# circuit.net
KiCad netlist of a schematic drawn in EAGLE
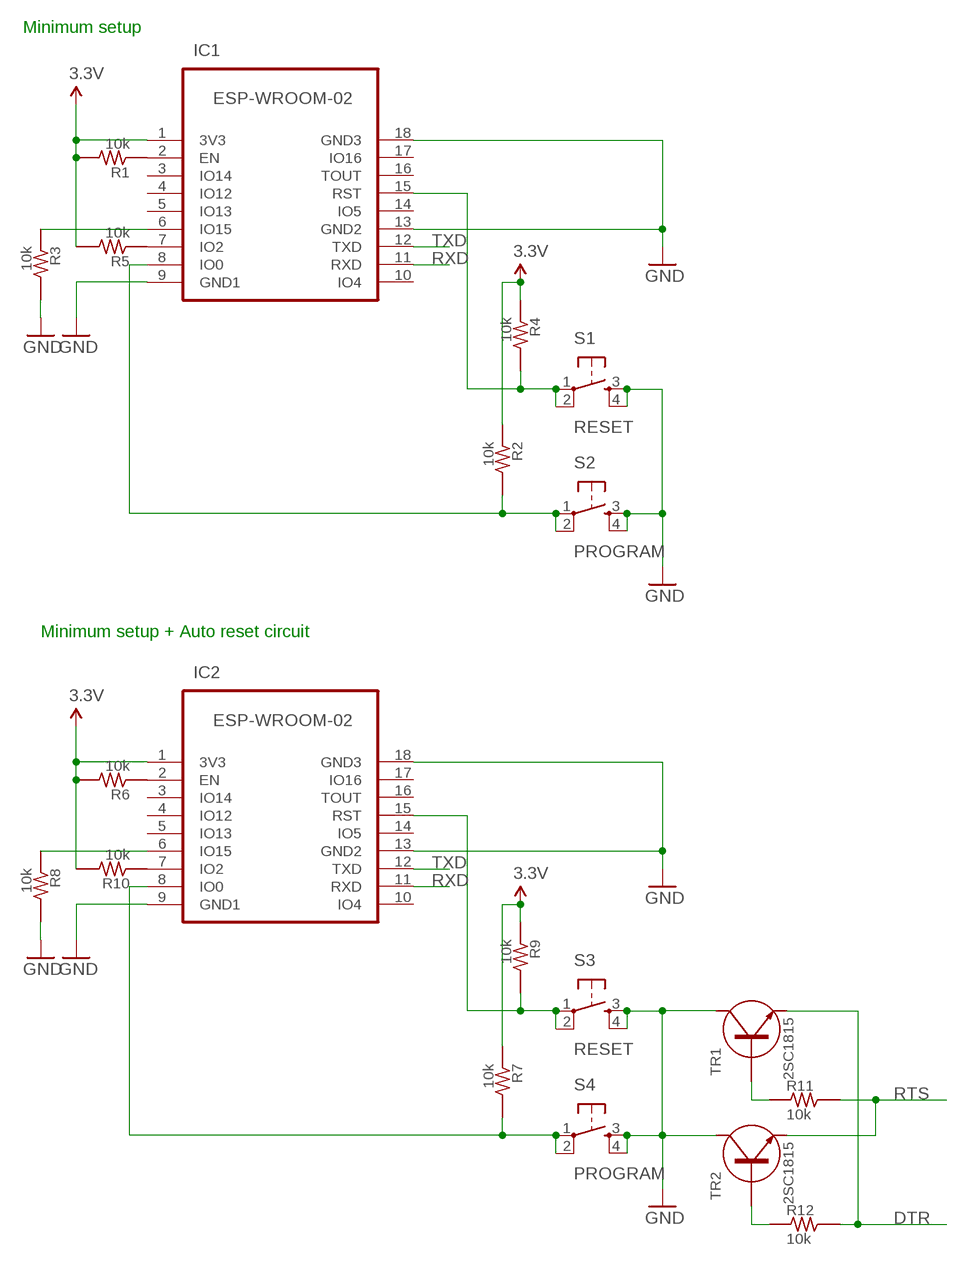
[diagram p0: schematic, sheet 1]

(export (version "E")
  (design (tool "Eeschema 10.0.6"))
  (components
    (comp (ref "IC1")
      (value "ESP-WROOM-02")
      (footprint "eagle-import:ESP-WROOM-02")
      (libsource (lib "eagle-import") (part "ESP-WROOM-02"))
    )
    (comp (ref "IC2")
      (value "ESP-WROOM-02")
      (footprint "eagle-import:ESP-WROOM-02")
      (libsource (lib "eagle-import") (part "ESP-WROOM-02"))
    )
    (comp (ref "R1")
      (value "10k")
      (footprint "eagle-import:1_4W-7.62H")
      (libsource (lib "eagle-import") (part "R-1/4W-07.62"))
    )
    (comp (ref "R2")
      (value "10k")
      (footprint "eagle-import:1_4W-7.62H")
      (libsource (lib "eagle-import") (part "R-1/4W-07.62"))
    )
    (comp (ref "R3")
      (value "10k")
      (footprint "eagle-import:1_4W-7.62H")
      (libsource (lib "eagle-import") (part "R-1/4W-07.62"))
    )
    (comp (ref "R4")
      (value "10k")
      (footprint "eagle-import:1_4W-7.62H")
      (libsource (lib "eagle-import") (part "R-1/4W-07.62"))
    )
    (comp (ref "R5")
      (value "10k")
      (footprint "eagle-import:1_4W-7.62H")
      (libsource (lib "eagle-import") (part "R-1/4W-07.62"))
    )
    (comp (ref "R6")
      (value "10k")
      (footprint "eagle-import:1_4W-7.62H")
      (libsource (lib "eagle-import") (part "R-1/4W-07.62"))
    )
    (comp (ref "R7")
      (value "10k")
      (footprint "eagle-import:1_4W-7.62H")
      (libsource (lib "eagle-import") (part "R-1/4W-07.62"))
    )
    (comp (ref "R8")
      (value "10k")
      (footprint "eagle-import:1_4W-7.62H")
      (libsource (lib "eagle-import") (part "R-1/4W-07.62"))
    )
    (comp (ref "R9")
      (value "10k")
      (footprint "eagle-import:1_4W-7.62H")
      (libsource (lib "eagle-import") (part "R-1/4W-07.62"))
    )
    (comp (ref "R10")
      (value "10k")
      (footprint "eagle-import:1_4W-7.62H")
      (libsource (lib "eagle-import") (part "R-1/4W-07.62"))
    )
    (comp (ref "R11")
      (value "10k")
      (footprint "eagle-import:1_4W-7.62H")
      (libsource (lib "eagle-import") (part "R-1/4W-07.62"))
    )
    (comp (ref "R12")
      (value "10k")
      (footprint "eagle-import:1_4W-7.62H")
      (libsource (lib "eagle-import") (part "R-1/4W-07.62"))
    )
    (comp (ref "S1")
      (value "RESET")
      (footprint "eagle-import:TACTILE-PTH")
      (libsource (lib "eagle-import") (part "TAC_SWITCHPTH"))
    )
    (comp (ref "S2")
      (value "PROGRAM")
      (footprint "eagle-import:TACTILE-PTH")
      (libsource (lib "eagle-import") (part "TAC_SWITCHPTH"))
    )
    (comp (ref "S3")
      (value "RESET")
      (footprint "eagle-import:TACTILE-PTH")
      (libsource (lib "eagle-import") (part "TAC_SWITCHPTH"))
    )
    (comp (ref "S4")
      (value "PROGRAM")
      (footprint "eagle-import:TACTILE-PTH")
      (libsource (lib "eagle-import") (part "TAC_SWITCHPTH"))
    )
    (comp (ref "TR1")
      (value "2SC1815")
      (footprint "eagle-import:TO-92")
      (libsource (lib "eagle-import") (part "TR-NPN-TO-92-ECB"))
    )
    (comp (ref "TR2")
      (value "2SC1815")
      (footprint "eagle-import:TO-92")
      (libsource (lib "eagle-import") (part "TR-NPN-TO-92-ECB"))
    )
  )
  (nets
    (net (code "1") (name "/DTR") (class "Default")
      (node (ref "R12") (pin "PAD2") (pinfunction "2_PAD2") (pintype "passive"))
      (node (ref "TR1") (pin "1") (pinfunction "E_1") (pintype "passive"))
    )
    (net (code "2") (name "/RTS") (class "Default")
      (node (ref "R11") (pin "PAD2") (pinfunction "2_PAD2") (pintype "passive"))
      (node (ref "TR2") (pin "1") (pinfunction "E_1") (pintype "passive"))
    )
    (net (code "3") (name "/RXD") (class "Default")
      (node (ref "IC1") (pin "11") (pinfunction "RXD_11") (pintype "bidirectional"))
      (node (ref "IC2") (pin "11") (pinfunction "RXD_11") (pintype "bidirectional"))
    )
    (net (code "4") (name "/TXD") (class "Default")
      (node (ref "IC1") (pin "12") (pinfunction "TXD_12") (pintype "bidirectional"))
      (node (ref "IC2") (pin "12") (pinfunction "TXD_12") (pintype "bidirectional"))
    )
    (net (code "5") (name "3.3V") (class "Default")
      (node (ref "IC1") (pin "1") (pinfunction "3V3_1") (pintype "power_in"))
      (node (ref "IC2") (pin "1") (pinfunction "3V3_1") (pintype "power_in"))
      (node (ref "R1") (pin "PAD2") (pinfunction "2_PAD2") (pintype "passive"))
      (node (ref "R10") (pin "PAD2") (pinfunction "2_PAD2") (pintype "passive"))
      (node (ref "R2") (pin "PAD1") (pinfunction "1_PAD1") (pintype "passive"))
      (node (ref "R4") (pin "PAD1") (pinfunction "1_PAD1") (pintype "passive"))
      (node (ref "R5") (pin "PAD2") (pinfunction "2_PAD2") (pintype "passive"))
      (node (ref "R6") (pin "PAD2") (pinfunction "2_PAD2") (pintype "passive"))
      (node (ref "R7") (pin "PAD1") (pinfunction "1_PAD1") (pintype "passive"))
      (node (ref "R9") (pin "PAD1") (pinfunction "1_PAD1") (pintype "passive"))
    )
    (net (code "6") (name "GND") (class "Default")
      (node (ref "IC1") (pin "13") (pinfunction "GND2_13") (pintype "power_in"))
      (node (ref "IC1") (pin "18") (pinfunction "GND3_18") (pintype "power_in"))
      (node (ref "IC1") (pin "9") (pinfunction "GND1_9") (pintype "power_in"))
      (node (ref "IC2") (pin "13") (pinfunction "GND2_13") (pintype "power_in"))
      (node (ref "IC2") (pin "18") (pinfunction "GND3_18") (pintype "power_in"))
      (node (ref "IC2") (pin "9") (pinfunction "GND1_9") (pintype "power_in"))
      (node (ref "R3") (pin "PAD2") (pinfunction "2_PAD2") (pintype "passive"))
      (node (ref "R8") (pin "PAD2") (pinfunction "2_PAD2") (pintype "passive"))
      (node (ref "S1") (pin "3") (pinfunction "3_3") (pintype "passive"))
      (node (ref "S1") (pin "4") (pinfunction "4_4") (pintype "passive"))
      (node (ref "S2") (pin "3") (pinfunction "3_3") (pintype "passive"))
      (node (ref "S2") (pin "4") (pinfunction "4_4") (pintype "passive"))
      (node (ref "S3") (pin "3") (pinfunction "3_3") (pintype "passive"))
      (node (ref "S3") (pin "4") (pinfunction "4_4") (pintype "passive"))
      (node (ref "S4") (pin "3") (pinfunction "3_3") (pintype "passive"))
      (node (ref "S4") (pin "4") (pinfunction "4_4") (pintype "passive"))
      (node (ref "TR1") (pin "2") (pinfunction "C_2") (pintype "passive"))
      (node (ref "TR2") (pin "2") (pinfunction "C_2") (pintype "passive"))
    )
    (net (code "7") (name "Net-(IC1-EN)") (class "Default")
      (node (ref "IC1") (pin "2") (pinfunction "EN_2") (pintype "bidirectional"))
      (node (ref "R1") (pin "PAD1") (pinfunction "1_PAD1") (pintype "passive"))
    )
    (net (code "8") (name "Net-(IC1-IO0)") (class "Default")
      (node (ref "IC1") (pin "8") (pinfunction "IO0_8") (pintype "bidirectional"))
      (node (ref "R2") (pin "PAD2") (pinfunction "2_PAD2") (pintype "passive"))
      (node (ref "S2") (pin "1") (pinfunction "1_1") (pintype "passive"))
      (node (ref "S2") (pin "2") (pinfunction "2_2") (pintype "passive"))
    )
    (net (code "9") (name "Net-(IC1-IO2)") (class "Default")
      (node (ref "IC1") (pin "7") (pinfunction "IO2_7") (pintype "bidirectional"))
      (node (ref "R5") (pin "PAD1") (pinfunction "1_PAD1") (pintype "passive"))
    )
    (net (code "10") (name "Net-(IC1-IO15)") (class "Default")
      (node (ref "IC1") (pin "6") (pinfunction "IO15_6") (pintype "bidirectional"))
      (node (ref "R3") (pin "PAD1") (pinfunction "1_PAD1") (pintype "passive"))
    )
    (net (code "11") (name "Net-(IC1-RST)") (class "Default")
      (node (ref "IC1") (pin "15") (pinfunction "RST_15") (pintype "bidirectional"))
      (node (ref "R4") (pin "PAD2") (pinfunction "2_PAD2") (pintype "passive"))
      (node (ref "S1") (pin "1") (pinfunction "1_1") (pintype "passive"))
      (node (ref "S1") (pin "2") (pinfunction "2_2") (pintype "passive"))
    )
    (net (code "12") (name "Net-(IC2-EN)") (class "Default")
      (node (ref "IC2") (pin "2") (pinfunction "EN_2") (pintype "bidirectional"))
      (node (ref "R6") (pin "PAD1") (pinfunction "1_PAD1") (pintype "passive"))
    )
    (net (code "13") (name "Net-(IC2-IO0)") (class "Default")
      (node (ref "IC2") (pin "8") (pinfunction "IO0_8") (pintype "bidirectional"))
      (node (ref "R7") (pin "PAD2") (pinfunction "2_PAD2") (pintype "passive"))
      (node (ref "S4") (pin "1") (pinfunction "1_1") (pintype "passive"))
      (node (ref "S4") (pin "2") (pinfunction "2_2") (pintype "passive"))
    )
    (net (code "14") (name "Net-(IC2-IO2)") (class "Default")
      (node (ref "IC2") (pin "7") (pinfunction "IO2_7") (pintype "bidirectional"))
      (node (ref "R10") (pin "PAD1") (pinfunction "1_PAD1") (pintype "passive"))
    )
    (net (code "15") (name "Net-(IC2-IO15)") (class "Default")
      (node (ref "IC2") (pin "6") (pinfunction "IO15_6") (pintype "bidirectional"))
      (node (ref "R8") (pin "PAD1") (pinfunction "1_PAD1") (pintype "passive"))
    )
    (net (code "16") (name "Net-(IC2-RST)") (class "Default")
      (node (ref "IC2") (pin "15") (pinfunction "RST_15") (pintype "bidirectional"))
      (node (ref "R9") (pin "PAD2") (pinfunction "2_PAD2") (pintype "passive"))
      (node (ref "S3") (pin "1") (pinfunction "1_1") (pintype "passive"))
      (node (ref "S3") (pin "2") (pinfunction "2_2") (pintype "passive"))
    )
    (net (code "17") (name "Net-(R11-1)") (class "Default")
      (node (ref "R11") (pin "PAD1") (pinfunction "1_PAD1") (pintype "passive"))
      (node (ref "TR1") (pin "3") (pinfunction "B_3") (pintype "passive"))
    )
    (net (code "18") (name "Net-(R12-1)") (class "Default")
      (node (ref "R12") (pin "PAD1") (pinfunction "1_PAD1") (pintype "passive"))
      (node (ref "TR2") (pin "3") (pinfunction "B_3") (pintype "passive"))
    )
    (net (code "19") (name "unconnected-(IC1-IO4-Pad10)") (class "Default")
      (node (ref "IC1") (pin "10") (pinfunction "IO4_10") (pintype "bidirectional"))
    )
    (net (code "20") (name "unconnected-(IC1-IO5-Pad14)") (class "Default")
      (node (ref "IC1") (pin "14") (pinfunction "IO5_14") (pintype "open_collector"))
    )
    (net (code "21") (name "unconnected-(IC1-IO12-Pad4)") (class "Default")
      (node (ref "IC1") (pin "4") (pinfunction "IO12_4") (pintype "bidirectional"))
    )
    (net (code "22") (name "unconnected-(IC1-IO13-Pad5)") (class "Default")
      (node (ref "IC1") (pin "5") (pinfunction "IO13_5") (pintype "bidirectional"))
    )
    (net (code "23") (name "unconnected-(IC1-IO14-Pad3)") (class "Default")
      (node (ref "IC1") (pin "3") (pinfunction "IO14_3") (pintype "bidirectional"))
    )
    (net (code "24") (name "unconnected-(IC1-IO16-Pad17)") (class "Default")
      (node (ref "IC1") (pin "17") (pinfunction "IO16_17") (pintype "bidirectional"))
    )
    (net (code "25") (name "unconnected-(IC1-TOUT-Pad16)") (class "Default")
      (node (ref "IC1") (pin "16") (pinfunction "TOUT_16") (pintype "bidirectional"))
    )
    (net (code "26") (name "unconnected-(IC2-IO4-Pad10)") (class "Default")
      (node (ref "IC2") (pin "10") (pinfunction "IO4_10") (pintype "bidirectional"))
    )
    (net (code "27") (name "unconnected-(IC2-IO5-Pad14)") (class "Default")
      (node (ref "IC2") (pin "14") (pinfunction "IO5_14") (pintype "open_collector"))
    )
    (net (code "28") (name "unconnected-(IC2-IO12-Pad4)") (class "Default")
      (node (ref "IC2") (pin "4") (pinfunction "IO12_4") (pintype "bidirectional"))
    )
    (net (code "29") (name "unconnected-(IC2-IO13-Pad5)") (class "Default")
      (node (ref "IC2") (pin "5") (pinfunction "IO13_5") (pintype "bidirectional"))
    )
    (net (code "30") (name "unconnected-(IC2-IO14-Pad3)") (class "Default")
      (node (ref "IC2") (pin "3") (pinfunction "IO14_3") (pintype "bidirectional"))
    )
    (net (code "31") (name "unconnected-(IC2-IO16-Pad17)") (class "Default")
      (node (ref "IC2") (pin "17") (pinfunction "IO16_17") (pintype "bidirectional"))
    )
    (net (code "32") (name "unconnected-(IC2-TOUT-Pad16)") (class "Default")
      (node (ref "IC2") (pin "16") (pinfunction "TOUT_16") (pintype "bidirectional"))
    )
  )
)
